# growth_v1.net
KiCad netlist of a schematic drawn in EAGLE
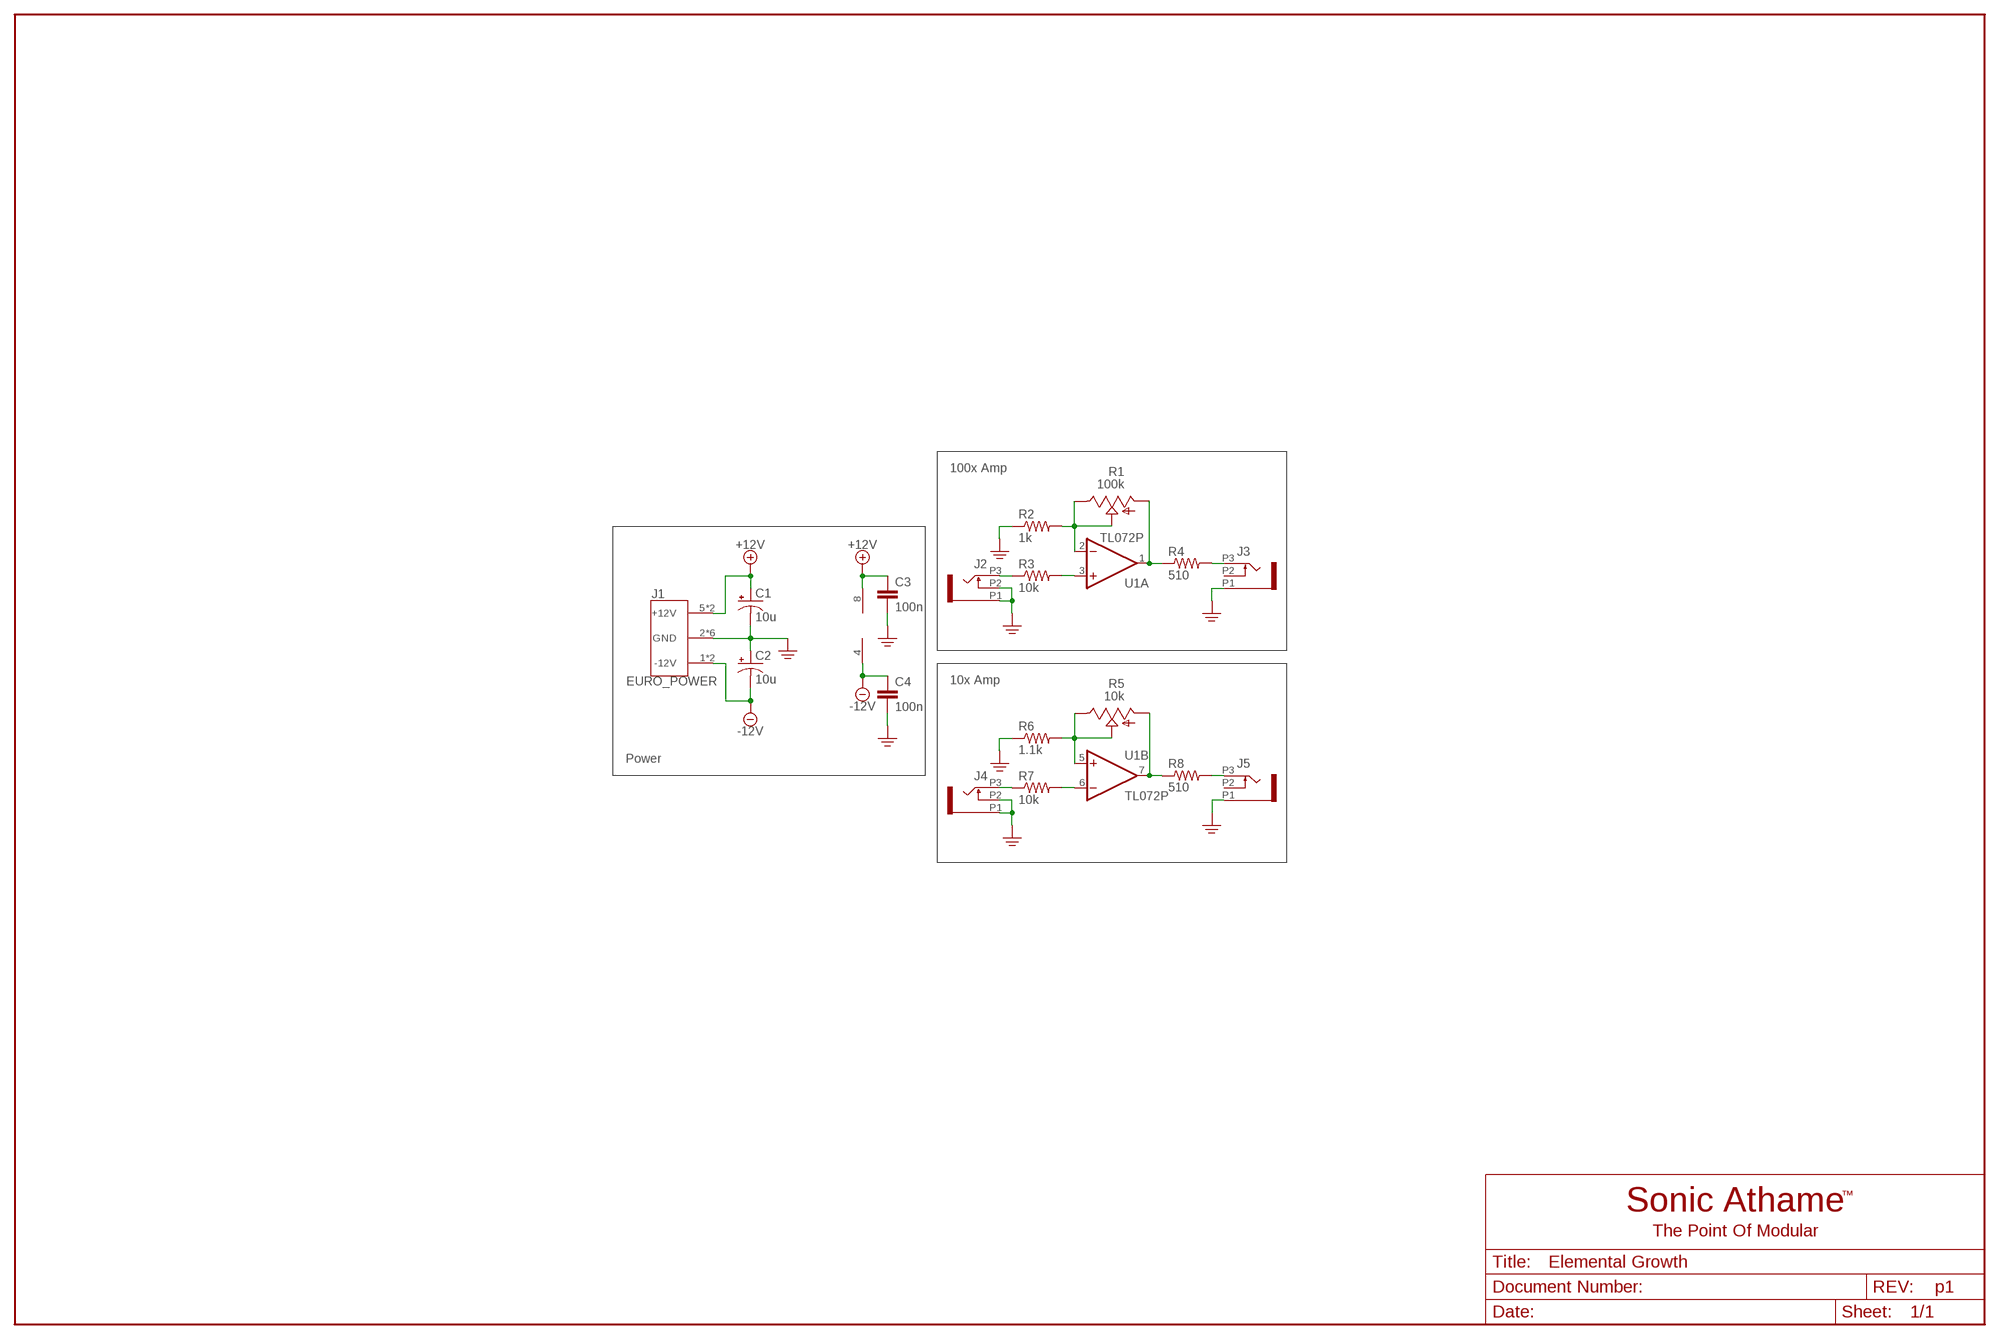
[diagram p0: schematic, sheet 1]

(export (version "E")
  (design (tool "Eeschema 10.0.6"))
  (components
    (comp (ref "C1")
      (value "10u")
      (footprint "eagle-import:TT2D5L_FLIP")
      (libsource (lib "eagle-import") (part "CAP_POLLYTIC_H_L"))
    )
    (comp (ref "C2")
      (value "10u")
      (footprint "eagle-import:TT2D5L_FLIP")
      (libsource (lib "eagle-import") (part "CAP_POLLYTIC_H_L"))
    )
    (comp (ref "C3")
      (value "100n")
      (footprint "eagle-import:C025-024X044")
      (libsource (lib "eagle-import") (part "CAP_NONPOL025-024X044"))
    )
    (comp (ref "C4")
      (value "100n")
      (footprint "eagle-import:C025-024X044")
      (libsource (lib "eagle-import") (part "CAP_NONPOL025-024X044"))
    )
    (comp (ref "J1")
      (value "EURO_POWER")
      (footprint "eagle-import:EURO_POWER")
      (libsource (lib "eagle-import") (part "EURO_POWER"))
    )
    (comp (ref "J2")
      (value "WQP-PJ398SM6")
      (footprint "eagle-import:WQP_PJ_301M6")
      (libsource (lib "eagle-import") (part "WQP-PJ398SM6"))
    )
    (comp (ref "J3")
      (value "WQP-PJ398SM6")
      (footprint "eagle-import:WQP_PJ_301M6")
      (libsource (lib "eagle-import") (part "WQP-PJ398SM6"))
    )
    (comp (ref "J4")
      (value "WQP-PJ398SM6")
      (footprint "eagle-import:WQP_PJ_301M6")
      (libsource (lib "eagle-import") (part "WQP-PJ398SM6"))
    )
    (comp (ref "J5")
      (value "WQP-PJ398SM6")
      (footprint "eagle-import:WQP_PJ_301M6")
      (libsource (lib "eagle-import") (part "WQP-PJ398SM6"))
    )
    (comp (ref "R1")
      (value "100k")
      (footprint "eagle-import:ALPHA_POT_VERTICAL")
      (libsource (lib "eagle-import") (part "ALPHA_POT_VERTICALVERTICAL"))
    )
    (comp (ref "R2")
      (value "1k")
      (footprint "eagle-import:0207_2V")
      (libsource (lib "eagle-import") (part "RESISTOR0207/2V"))
    )
    (comp (ref "R3")
      (value "10k")
      (footprint "eagle-import:0207_2V")
      (libsource (lib "eagle-import") (part "RESISTOR0207/2V"))
    )
    (comp (ref "R4")
      (value "510")
      (footprint "eagle-import:0207_2V")
      (libsource (lib "eagle-import") (part "RESISTOR0207/2V"))
    )
    (comp (ref "R5")
      (value "10k")
      (footprint "eagle-import:ALPHA_POT_VERTICAL")
      (libsource (lib "eagle-import") (part "ALPHA_POT_VERTICALVERTICAL"))
    )
    (comp (ref "R6")
      (value "1.1k")
      (footprint "eagle-import:0207_2V")
      (libsource (lib "eagle-import") (part "RESISTOR0207/2V"))
    )
    (comp (ref "R7")
      (value "10k")
      (footprint "eagle-import:0207_2V")
      (libsource (lib "eagle-import") (part "RESISTOR0207/2V"))
    )
    (comp (ref "R8")
      (value "510")
      (footprint "eagle-import:0207_2V")
      (libsource (lib "eagle-import") (part "RESISTOR0207/2V"))
    )
    (comp (ref "U1")
      (value "TL072P")
      (footprint "eagle-import:DIL08")
      (libsource (lib "eagle-import") (part "TL072P"))
    )
  )
  (nets
    (net (code "1") (name "+12V") (class "Default")
      (node (ref "C1") (pin "+") (pinfunction "+_+") (pintype "passive"))
      (node (ref "C3") (pin "1") (pinfunction "1_1") (pintype "passive"))
      (node (ref "J1") (pin "5") (pinfunction "+12V_5") (pintype "bidirectional"))
      (node (ref "J1") (pin "6") (pinfunction "+12V_6") (pintype "bidirectional"))
      (node (ref "U1") (pin "8") (pinfunction "V+_8") (pintype "power_in"))
    )
    (net (code "2") (name "-12V") (class "Default")
      (node (ref "C2") (pin "-") (pinfunction "-_-") (pintype "passive"))
      (node (ref "C4") (pin "1") (pinfunction "1_1") (pintype "passive"))
      (node (ref "J1") (pin "1") (pinfunction "-12V_1") (pintype "bidirectional"))
      (node (ref "J1") (pin "10") (pinfunction "-12V_10") (pintype "bidirectional"))
      (node (ref "U1") (pin "4") (pinfunction "V-_4") (pintype "power_in"))
    )
    (net (code "3") (name "GND") (class "Default")
      (node (ref "C1") (pin "-") (pinfunction "-_-") (pintype "passive"))
      (node (ref "C2") (pin "+") (pinfunction "+_+") (pintype "passive"))
      (node (ref "C3") (pin "2") (pinfunction "2_2") (pintype "passive"))
      (node (ref "C4") (pin "2") (pinfunction "2_2") (pintype "passive"))
      (node (ref "J1") (pin "2") (pinfunction "GND_2") (pintype "bidirectional"))
      (node (ref "J1") (pin "3") (pinfunction "GND_3") (pintype "bidirectional"))
      (node (ref "J1") (pin "4") (pinfunction "GND_4") (pintype "bidirectional"))
      (node (ref "J1") (pin "7") (pinfunction "GND_7") (pintype "bidirectional"))
      (node (ref "J1") (pin "8") (pinfunction "GND_8") (pintype "bidirectional"))
      (node (ref "J1") (pin "9") (pinfunction "GND_9") (pintype "bidirectional"))
      (node (ref "J2") (pin "P1") (pinfunction "1_P1") (pintype "passive"))
      (node (ref "J2") (pin "P2") (pinfunction "2_P2") (pintype "passive"))
      (node (ref "J3") (pin "P1") (pinfunction "1_P1") (pintype "passive"))
      (node (ref "J4") (pin "P1") (pinfunction "1_P1") (pintype "passive"))
      (node (ref "J4") (pin "P2") (pinfunction "2_P2") (pintype "passive"))
      (node (ref "J5") (pin "P1") (pinfunction "1_P1") (pintype "passive"))
      (node (ref "R2") (pin "1") (pinfunction "1_1") (pintype "passive"))
      (node (ref "R6") (pin "1") (pinfunction "1_1") (pintype "passive"))
    )
    (net (code "4") (name "Net-(J2-3)") (class "Default")
      (node (ref "J2") (pin "P3") (pinfunction "3_P3") (pintype "passive"))
      (node (ref "R3") (pin "1") (pinfunction "1_1") (pintype "passive"))
    )
    (net (code "5") (name "Net-(J3-3)") (class "Default")
      (node (ref "J3") (pin "P3") (pinfunction "3_P3") (pintype "passive"))
      (node (ref "R4") (pin "2") (pinfunction "2_2") (pintype "passive"))
    )
    (net (code "6") (name "Net-(J4-3)") (class "Default")
      (node (ref "J4") (pin "P3") (pinfunction "3_P3") (pintype "passive"))
      (node (ref "R7") (pin "1") (pinfunction "1_1") (pintype "passive"))
    )
    (net (code "7") (name "Net-(J5-3)") (class "Default")
      (node (ref "J5") (pin "P3") (pinfunction "3_P3") (pintype "passive"))
      (node (ref "R8") (pin "2") (pinfunction "2_2") (pintype "passive"))
    )
    (net (code "8") (name "Net-(R1-A)") (class "Default")
      (node (ref "R1") (pin "P$3") (pinfunction "A_P$3") (pintype "passive"))
      (node (ref "R4") (pin "1") (pinfunction "1_1") (pintype "passive"))
      (node (ref "U1") (pin "1") (pinfunction "OUT_1") (pintype "output"))
    )
    (net (code "9") (name "Net-(R1-E)") (class "Default")
      (node (ref "R1") (pin "P$1") (pinfunction "E_P$1") (pintype "passive"))
      (node (ref "R1") (pin "P$2") (pinfunction "S_P$2") (pintype "passive"))
      (node (ref "R2") (pin "2") (pinfunction "2_2") (pintype "passive"))
      (node (ref "U1") (pin "2") (pinfunction "-IN_2") (pintype "input"))
    )
    (net (code "10") (name "Net-(R5-A)") (class "Default")
      (node (ref "R5") (pin "P$3") (pinfunction "A_P$3") (pintype "passive"))
      (node (ref "R8") (pin "1") (pinfunction "1_1") (pintype "passive"))
      (node (ref "U1") (pin "7") (pinfunction "OUT_7") (pintype "output"))
    )
    (net (code "11") (name "Net-(R5-E)") (class "Default")
      (node (ref "R5") (pin "P$1") (pinfunction "E_P$1") (pintype "passive"))
      (node (ref "R5") (pin "P$2") (pinfunction "S_P$2") (pintype "passive"))
      (node (ref "R6") (pin "2") (pinfunction "2_2") (pintype "passive"))
      (node (ref "U1") (pin "5") (pinfunction "+IN_5") (pintype "input"))
    )
    (net (code "12") (name "Net-(U1A-+IN)") (class "Default")
      (node (ref "R3") (pin "2") (pinfunction "2_2") (pintype "passive"))
      (node (ref "U1") (pin "3") (pinfunction "+IN_3") (pintype "input"))
    )
    (net (code "13") (name "Net-(U1B--IN)") (class "Default")
      (node (ref "R7") (pin "2") (pinfunction "2_2") (pintype "passive"))
      (node (ref "U1") (pin "6") (pinfunction "-IN_6") (pintype "input"))
    )
    (net (code "14") (name "unconnected-(J3-2-PadP2)") (class "Default")
      (node (ref "J3") (pin "P2") (pinfunction "2_P2") (pintype "passive"))
    )
    (net (code "15") (name "unconnected-(J5-2-PadP2)") (class "Default")
      (node (ref "J5") (pin "P2") (pinfunction "2_P2") (pintype "passive"))
    )
  )
)
